# PD_FDS100_v1_0.net
KiCad netlist of a schematic drawn in EAGLE
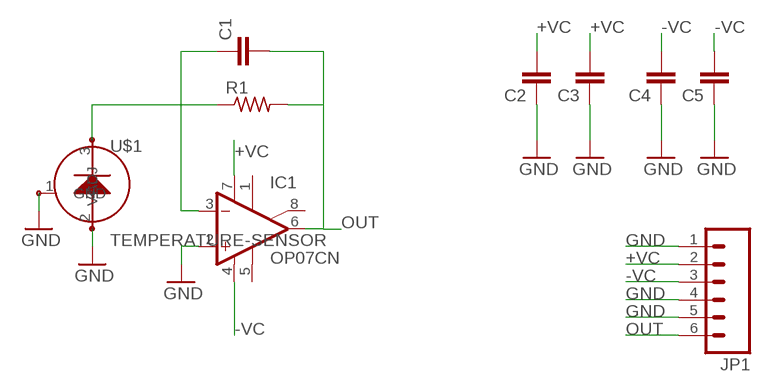
[diagram p0: schematic, sheet 1]

(export (version "E")
  (design (tool "Eeschema 10.0.6"))
  (components
    (comp (ref "C1")
      (value "CAPPTH1")
      (footprint "eagle-import:CAP-PTH-5MM")
      (libsource (lib "eagle-import") (part "CAPPTH1"))
    )
    (comp (ref "C2")
      (value "CAPPTH1")
      (footprint "eagle-import:CAP-PTH-5MM")
      (libsource (lib "eagle-import") (part "CAPPTH1"))
    )
    (comp (ref "C3")
      (value "CAPPTH1")
      (footprint "eagle-import:CAP-PTH-5MM")
      (libsource (lib "eagle-import") (part "CAPPTH1"))
    )
    (comp (ref "C4")
      (value "CAPPTH1")
      (footprint "eagle-import:CAP-PTH-5MM")
      (libsource (lib "eagle-import") (part "CAPPTH1"))
    )
    (comp (ref "C5")
      (value "CAPPTH1")
      (footprint "eagle-import:CAP-PTH-5MM")
      (libsource (lib "eagle-import") (part "CAPPTH1"))
    )
    (comp (ref "IC1")
      (value "OP07CN")
      (footprint "eagle-import:DIL08")
      (libsource (lib "eagle-import") (part "OP07NC"))
    )
    (comp (ref "JP1")
      (value "M06NO_SILK")
      (footprint "eagle-import:1X06_NO_SILK")
      (libsource (lib "eagle-import") (part "M06NO_SILK"))
    )
    (comp (ref "R1")
      (value "R-US_0207/10")
      (footprint "eagle-import:0207_10")
      (libsource (lib "eagle-import") (part "R-US_0207/10"))
    )
    (comp (ref "U$1")
      (value "TEMPERATURE-SENSOR")
      (footprint "eagle-import:TO-92")
      (libsource (lib "eagle-import") (part "TEMPERATURE-SENSOR"))
    )
  )
  (nets
    (net (code "1") (name "/+VC") (class "Default")
      (node (ref "C2") (pin "2") (pinfunction "2_2") (pintype "passive"))
      (node (ref "C3") (pin "2") (pinfunction "2_2") (pintype "passive"))
      (node (ref "IC1") (pin "7") (pinfunction "V+_7") (pintype "power_in"))
      (node (ref "JP1") (pin "2") (pinfunction "2_2") (pintype "passive"))
    )
    (net (code "2") (name "/-VC") (class "Default")
      (node (ref "C4") (pin "2") (pinfunction "2_2") (pintype "passive"))
      (node (ref "C5") (pin "2") (pinfunction "2_2") (pintype "passive"))
      (node (ref "IC1") (pin "4") (pinfunction "V-_4") (pintype "power_in"))
      (node (ref "JP1") (pin "3") (pinfunction "3_3") (pintype "passive"))
    )
    (net (code "3") (name "/OUT") (class "Default")
      (node (ref "C1") (pin "2") (pinfunction "2_2") (pintype "passive"))
      (node (ref "IC1") (pin "6") (pinfunction "OUT_6") (pintype "output"))
      (node (ref "JP1") (pin "6") (pinfunction "6_6") (pintype "passive"))
      (node (ref "R1") (pin "2") (pinfunction "2_2") (pintype "passive"))
    )
    (net (code "4") (name "GND") (class "Default")
      (node (ref "C2") (pin "1") (pinfunction "1_1") (pintype "passive"))
      (node (ref "C3") (pin "1") (pinfunction "1_1") (pintype "passive"))
      (node (ref "C4") (pin "1") (pinfunction "1_1") (pintype "passive"))
      (node (ref "C5") (pin "1") (pinfunction "1_1") (pintype "passive"))
      (node (ref "IC1") (pin "2") (pinfunction "-IN_2") (pintype "input"))
      (node (ref "JP1") (pin "1") (pinfunction "1_1") (pintype "passive"))
      (node (ref "JP1") (pin "4") (pinfunction "4_4") (pintype "passive"))
      (node (ref "JP1") (pin "5") (pinfunction "5_5") (pintype "passive"))
      (node (ref "U$1") (pin "1") (pinfunction "GND_1") (pintype "bidirectional"))
      (node (ref "U$1") (pin "2") (pinfunction "ADJ_2") (pintype "bidirectional"))
    )
    (net (code "5") (name "Net-(IC1-+IN)") (class "Default")
      (node (ref "C1") (pin "1") (pinfunction "1_1") (pintype "passive"))
      (node (ref "IC1") (pin "3") (pinfunction "+IN_3") (pintype "input"))
      (node (ref "R1") (pin "1") (pinfunction "1_1") (pintype "passive"))
      (node (ref "U$1") (pin "3") (pinfunction "VCC_3") (pintype "bidirectional"))
    )
    (net (code "6") (name "unconnected-(IC1-ON1-Pad1)") (class "Default")
      (node (ref "IC1") (pin "1") (pinfunction "ON1_1") (pintype "passive"))
    )
    (net (code "7") (name "unconnected-(IC1-ON2-Pad8)") (class "Default")
      (node (ref "IC1") (pin "8") (pinfunction "ON2_8") (pintype "passive"))
    )
    (net (code "8") (name "unconnected-(IC1-OPT-Pad5)") (class "Default")
      (node (ref "IC1") (pin "5") (pinfunction "OPT_5") (pintype "passive"))
    )
  )
)
